# 4_cyber60-smk_periferals.net
KiCad netlist of a schematic drawn in Altium Designer
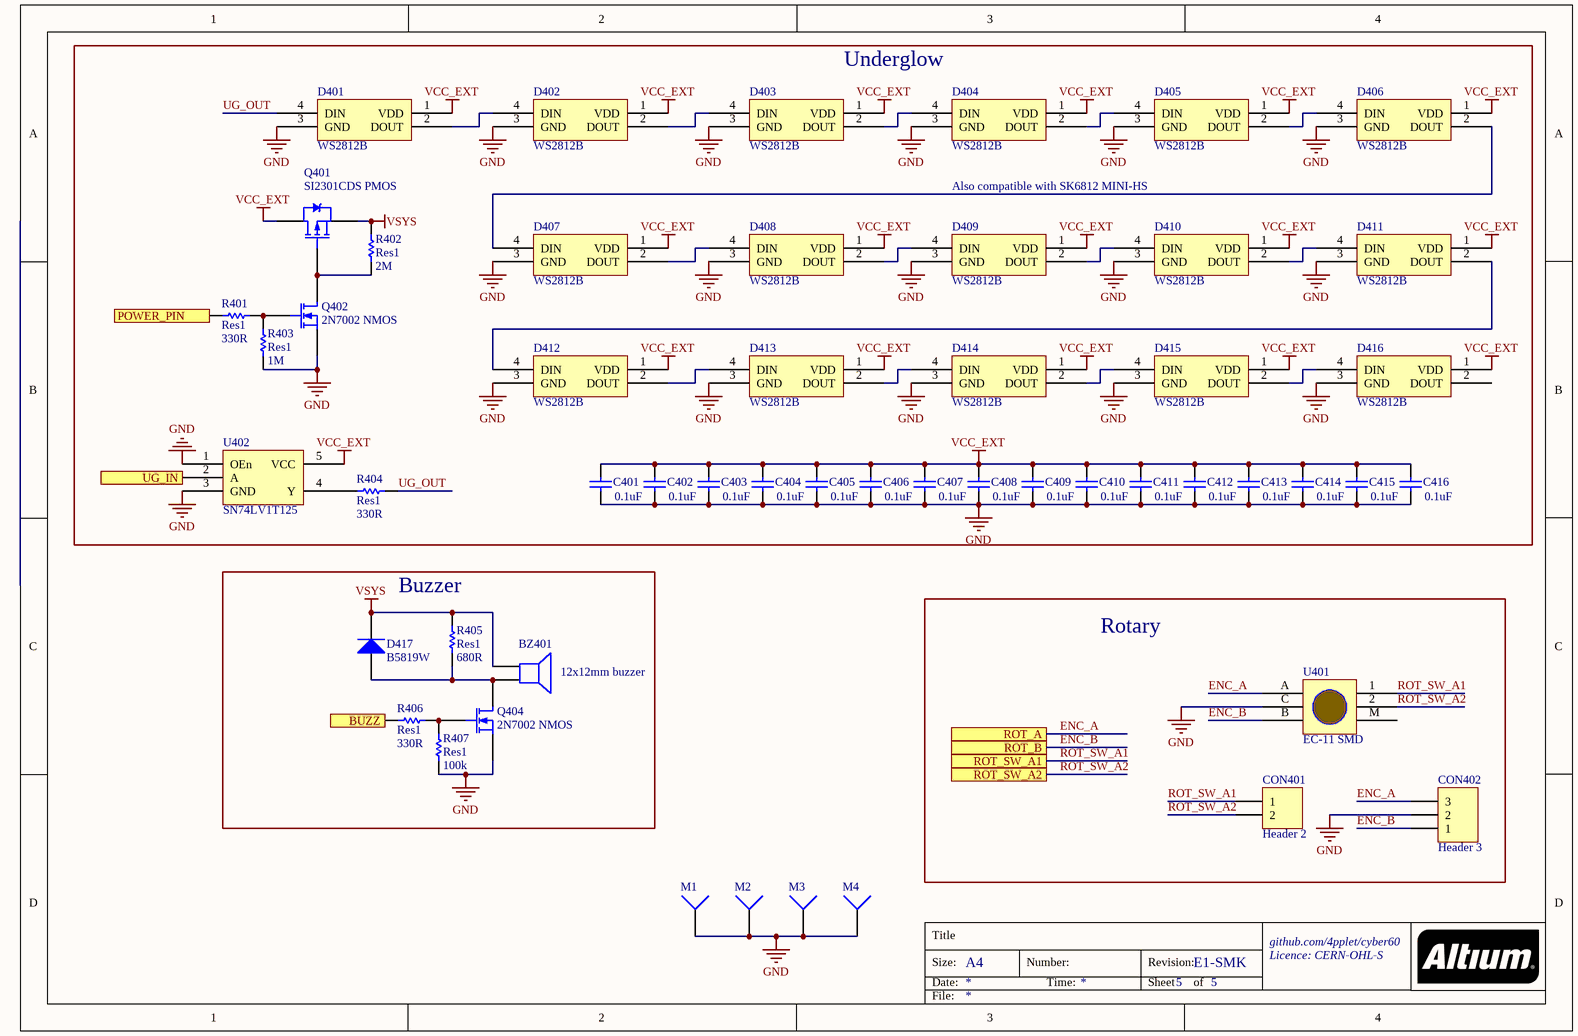
[diagram p0: 4_cyber60-smk_periferals.SchDoc]

(export (version "E")
  (design (tool "Eeschema 10.0.6"))
  (components
    (comp (ref "BZ401")
      (value "12x12mm buzzer")
      (footprint "buzzer 12x12")
      (description "Loudspeaker")
      (fields (field (name "LCSC PART #") "C409829") (field (name "MRF.PART") "YS-SBZ1230"))
      (libsource (lib "Miscellaneous Devices") (part "Speaker"))
    )
    (comp (ref "C401")
      (value "0.1uF")
      (footprint "C0603[1608]")
      (description "Capacitor")
      (fields (field (name "MFG") "KEMET") (field (name "LCSC PART #") "C14663"))
      (libsource (lib "Miscellaneous Devices") (part "Cap"))
    )
    (comp (ref "C402")
      (value "0.1uF")
      (footprint "C0603[1608]")
      (description "Capacitor")
      (fields (field (name "MFG") "KEMET") (field (name "LCSC PART #") "C14663"))
      (libsource (lib "Miscellaneous Devices") (part "Cap"))
    )
    (comp (ref "C403")
      (value "0.1uF")
      (footprint "C0603[1608]")
      (description "Capacitor")
      (fields (field (name "MFG") "KEMET") (field (name "LCSC PART #") "C14663"))
      (libsource (lib "Miscellaneous Devices") (part "Cap"))
    )
    (comp (ref "C404")
      (value "0.1uF")
      (footprint "C0603[1608]")
      (description "Capacitor")
      (fields (field (name "MFG") "KEMET") (field (name "LCSC PART #") "C14663"))
      (libsource (lib "Miscellaneous Devices") (part "Cap"))
    )
    (comp (ref "C405")
      (value "0.1uF")
      (footprint "C0603[1608]")
      (description "Capacitor")
      (fields (field (name "MFG") "KEMET") (field (name "LCSC PART #") "C14663"))
      (libsource (lib "Miscellaneous Devices") (part "Cap"))
    )
    (comp (ref "C406")
      (value "0.1uF")
      (footprint "C0603[1608]")
      (description "Capacitor")
      (fields (field (name "MFG") "KEMET") (field (name "LCSC PART #") "C14663"))
      (libsource (lib "Miscellaneous Devices") (part "Cap"))
    )
    (comp (ref "C407")
      (value "0.1uF")
      (footprint "C0603[1608]")
      (description "Capacitor")
      (fields (field (name "MFG") "KEMET") (field (name "LCSC PART #") "C14663"))
      (libsource (lib "Miscellaneous Devices") (part "Cap"))
    )
    (comp (ref "C408")
      (value "0.1uF")
      (footprint "C0603[1608]")
      (description "Capacitor")
      (fields (field (name "MFG") "KEMET") (field (name "LCSC PART #") "C14663"))
      (libsource (lib "Miscellaneous Devices") (part "Cap"))
    )
    (comp (ref "C409")
      (value "0.1uF")
      (footprint "C0603[1608]")
      (description "Capacitor")
      (fields (field (name "MFG") "KEMET") (field (name "LCSC PART #") "C14663"))
      (libsource (lib "Miscellaneous Devices") (part "Cap"))
    )
    (comp (ref "C410")
      (value "0.1uF")
      (footprint "C0603[1608]")
      (description "Capacitor")
      (fields (field (name "MFG") "KEMET") (field (name "LCSC PART #") "C14663"))
      (libsource (lib "Miscellaneous Devices") (part "Cap"))
    )
    (comp (ref "C411")
      (value "0.1uF")
      (footprint "C0603[1608]")
      (description "Capacitor")
      (fields (field (name "MFG") "KEMET") (field (name "LCSC PART #") "C14663"))
      (libsource (lib "Miscellaneous Devices") (part "Cap"))
    )
    (comp (ref "C412")
      (value "0.1uF")
      (footprint "C0603[1608]")
      (description "Capacitor")
      (fields (field (name "MFG") "KEMET") (field (name "LCSC PART #") "C14663"))
      (libsource (lib "Miscellaneous Devices") (part "Cap"))
    )
    (comp (ref "C413")
      (value "0.1uF")
      (footprint "C0603[1608]")
      (description "Capacitor")
      (fields (field (name "MFG") "KEMET") (field (name "LCSC PART #") "C14663"))
      (libsource (lib "Miscellaneous Devices") (part "Cap"))
    )
    (comp (ref "C414")
      (value "0.1uF")
      (footprint "C0603[1608]")
      (description "Capacitor")
      (fields (field (name "MFG") "KEMET") (field (name "LCSC PART #") "C14663"))
      (libsource (lib "Miscellaneous Devices") (part "Cap"))
    )
    (comp (ref "C415")
      (value "0.1uF")
      (footprint "C0603[1608]")
      (description "Capacitor")
      (fields (field (name "MFG") "KEMET") (field (name "LCSC PART #") "C14663"))
      (libsource (lib "Miscellaneous Devices") (part "Cap"))
    )
    (comp (ref "C416")
      (value "0.1uF")
      (footprint "C0603[1608]")
      (description "Capacitor")
      (fields (field (name "MFG") "KEMET") (field (name "LCSC PART #") "C14663"))
      (libsource (lib "Miscellaneous Devices") (part "Cap"))
    )
    (comp (ref "CON401")
      (value "Header 2")
      (footprint "HDR1X2")
      (description "Header, 2-Pin")
      (libsource (lib "Miscellaneous Connectors") (part "Header 2"))
    )
    (comp (ref "CON402")
      (value "Header 3")
      (footprint "HDR1X3")
      (description "Header, 3-Pin")
      (libsource (lib "Miscellaneous Connectors") (part "Header 3"))
    )
    (comp (ref "D401")
      (value "WS2812B")
      (footprint "WS2812B - 2020")
      (fields (field (name "LCSC PART #") "C965556") (field (name "MRF.PART") "WS2812C-2020"))
      (libsource (lib "Keebs") (part "WS2812B"))
    )
    (comp (ref "D402")
      (value "WS2812B")
      (footprint "WS2812B - 2020")
      (fields (field (name "LCSC PART #") "C965556") (field (name "MRF.PART") "WS2812C-2020"))
      (libsource (lib "Keebs") (part "WS2812B"))
    )
    (comp (ref "D403")
      (value "WS2812B")
      (footprint "WS2812B - 2020")
      (fields (field (name "LCSC PART #") "C965556") (field (name "MRF.PART") "WS2812C-2020"))
      (libsource (lib "Keebs") (part "WS2812B"))
    )
    (comp (ref "D404")
      (value "WS2812B")
      (footprint "WS2812B - 2020")
      (fields (field (name "LCSC PART #") "C965556") (field (name "MRF.PART") "WS2812C-2020"))
      (libsource (lib "Keebs") (part "WS2812B"))
    )
    (comp (ref "D405")
      (value "WS2812B")
      (footprint "WS2812B - 2020")
      (fields (field (name "LCSC PART #") "C965556") (field (name "MRF.PART") "WS2812C-2020"))
      (libsource (lib "Keebs") (part "WS2812B"))
    )
    (comp (ref "D406")
      (value "WS2812B")
      (footprint "WS2812B - 2020")
      (fields (field (name "LCSC PART #") "C965556") (field (name "MRF.PART") "WS2812C-2020"))
      (libsource (lib "Keebs") (part "WS2812B"))
    )
    (comp (ref "D407")
      (value "WS2812B")
      (footprint "WS2812B - 2020")
      (fields (field (name "LCSC PART #") "C965556") (field (name "MRF.PART") "WS2812C-2020"))
      (libsource (lib "Keebs") (part "WS2812B"))
    )
    (comp (ref "D408")
      (value "WS2812B")
      (footprint "WS2812B - 2020")
      (fields (field (name "LCSC PART #") "C965556") (field (name "MRF.PART") "WS2812C-2020"))
      (libsource (lib "Keebs") (part "WS2812B"))
    )
    (comp (ref "D409")
      (value "WS2812B")
      (footprint "WS2812B - 2020")
      (fields (field (name "LCSC PART #") "C965556") (field (name "MRF.PART") "WS2812C-2020"))
      (libsource (lib "Keebs") (part "WS2812B"))
    )
    (comp (ref "D410")
      (value "WS2812B")
      (footprint "WS2812B - 2020")
      (fields (field (name "LCSC PART #") "C965556") (field (name "MRF.PART") "WS2812C-2020"))
      (libsource (lib "Keebs") (part "WS2812B"))
    )
    (comp (ref "D411")
      (value "WS2812B")
      (footprint "WS2812B - 2020")
      (fields (field (name "LCSC PART #") "C965556") (field (name "MRF.PART") "WS2812C-2020"))
      (libsource (lib "Keebs") (part "WS2812B"))
    )
    (comp (ref "D412")
      (value "WS2812B")
      (footprint "WS2812B - 2020")
      (fields (field (name "LCSC PART #") "C965556") (field (name "MRF.PART") "WS2812C-2020"))
      (libsource (lib "Keebs") (part "WS2812B"))
    )
    (comp (ref "D413")
      (value "WS2812B")
      (footprint "WS2812B - 2020")
      (fields (field (name "LCSC PART #") "C965556") (field (name "MRF.PART") "WS2812C-2020"))
      (libsource (lib "Keebs") (part "WS2812B"))
    )
    (comp (ref "D414")
      (value "WS2812B")
      (footprint "WS2812B - 2020")
      (fields (field (name "LCSC PART #") "C965556") (field (name "MRF.PART") "WS2812C-2020"))
      (libsource (lib "Keebs") (part "WS2812B"))
    )
    (comp (ref "D415")
      (value "WS2812B")
      (footprint "WS2812B - 2020")
      (fields (field (name "LCSC PART #") "C965556") (field (name "MRF.PART") "WS2812C-2020"))
      (libsource (lib "Keebs") (part "WS2812B"))
    )
    (comp (ref "D416")
      (value "WS2812B")
      (footprint "WS2812B - 2020")
      (fields (field (name "LCSC PART #") "C965556") (field (name "MRF.PART") "WS2812C-2020"))
      (libsource (lib "Keebs") (part "WS2812B"))
    )
    (comp (ref "D417")
      (value "B5819W")
      (footprint "SOD-123")
      (description "Default Diode")
      (fields (field (name "LCSC PART #") "C8598"))
      (libsource (lib "Miscellaneous Devices") (part "Diode"))
    )
    (comp (ref "M1")
      (value "Socket")
      (footprint "mounting_hole")
      (fields (field (name "PUBLISHER") "Altium Limited"))
      (libsource (lib "Miscellaneous Connectors") (part "Socket"))
    )
    (comp (ref "M2")
      (value "Socket")
      (footprint "mounting_hole")
      (fields (field (name "PUBLISHER") "Altium Limited"))
      (libsource (lib "Miscellaneous Connectors") (part "Socket"))
    )
    (comp (ref "M3")
      (value "Socket")
      (footprint "mounting_hole")
      (fields (field (name "PUBLISHER") "Altium Limited"))
      (libsource (lib "Miscellaneous Connectors") (part "Socket"))
    )
    (comp (ref "M4")
      (value "Socket")
      (footprint "mounting_hole")
      (fields (field (name "PUBLISHER") "Altium Limited"))
      (libsource (lib "Miscellaneous Connectors") (part "Socket"))
    )
    (comp (ref "Q401")
      (value "SI2301CDS PMOS")
      (footprint "SOT-23-3")
      (description "P-Channel Power MOSFET")
      (fields (field (name "MRF.PART") "SI2301CDS-T1-GE3") (field (name "LCSC PART #") "C10487"))
      (libsource (lib "Miscellaneous Devices") (part "PMOS-2"))
    )
    (comp (ref "Q402")
      (value "2N7002 NMOS")
      (footprint "SOT-23-3")
      (description "N-Channel MOSFET")
      (fields (field (name "LCSC PART #") "C8545") (field (name "MRF.PART") "2N7002"))
      (libsource (lib "Miscellaneous Devices") (part "MOSFET-N"))
    )
    (comp (ref "Q404")
      (value "2N7002 NMOS")
      (footprint "SOT-23-3")
      (description "N-Channel MOSFET")
      (fields (field (name "LCSC PART #") "C8545") (field (name "MRF.PART") "2N7002"))
      (libsource (lib "Miscellaneous Devices") (part "MOSFET-N"))
    )
    (comp (ref "R401")
      (value "Res1")
      (footprint "R0603[1608]")
      (description "Resistor")
      (fields
        (field (name "ALTIUM_VALUE") "330R")
        (field (name "LCSC PART #") "C23138")
        (field (name "MRF.PART") "0603WAF3300T5E")
      )
      (libsource (lib "Miscellaneous Devices") (part "Res1"))
    )
    (comp (ref "R402")
      (value "Res1")
      (footprint "R0603[1608]")
      (description "Resistor")
      (fields
        (field (name "ALTIUM_VALUE") "2M")
        (field (name "MRF.PART") "0603WAF2004T5E")
        (field (name "LCSC PART #") "C22976")
      )
      (libsource (lib "Miscellaneous Devices") (part "Res1"))
    )
    (comp (ref "R403")
      (value "Res1")
      (footprint "R0603[1608]")
      (description "Resistor")
      (fields
        (field (name "ALTIUM_VALUE") "1M")
        (field (name "MRF.PART") "0603WAF1004T5E")
        (field (name "LCSC PART #") "C22935")
      )
      (libsource (lib "Miscellaneous Devices") (part "Res1"))
    )
    (comp (ref "R404")
      (value "Res1")
      (footprint "R0603[1608]")
      (description "Resistor")
      (fields
        (field (name "ALTIUM_VALUE") "330R")
        (field (name "LCSC PART #") "C23138")
        (field (name "MRF.PART") "0603WAF3300T5E")
      )
      (libsource (lib "Miscellaneous Devices") (part "Res1"))
    )
    (comp (ref "R405")
      (value "Res1")
      (footprint "R0603[1608]")
      (description "Resistor")
      (fields
        (field (name "ALTIUM_VALUE") "680R")
        (field (name "MRF.PART") "0603WAF6800T5E")
        (field (name "LCSC PART #") "C23228")
      )
      (libsource (lib "Miscellaneous Devices") (part "Res1"))
    )
    (comp (ref "R406")
      (value "Res1")
      (footprint "R0603[1608]")
      (description "Resistor")
      (fields
        (field (name "ALTIUM_VALUE") "330R")
        (field (name "LCSC PART #") "C23138")
        (field (name "MRF.PART") "0603WAF3300T5E")
      )
      (libsource (lib "Miscellaneous Devices") (part "Res1"))
    )
    (comp (ref "R407")
      (value "Res1")
      (footprint "R0603[1608]")
      (description "Resistor")
      (fields
        (field (name "ALTIUM_VALUE") "100k")
        (field (name "MRF.PART") "0603WAF1003T5E")
        (field (name "LCSC PART #") "C25803")
      )
      (libsource (lib "Miscellaneous Devices") (part "Res1"))
    )
    (comp (ref "U401") (value "EC-11 SMD") (footprint "EC11-SMD") (libsource (lib "Keebs") (part "EC-11")))
    (comp (ref "U402")
      (value "SN74LV1T125")
      (footprint "SOT-23-5")
      (description "SN74LV1T125 or SN74LV1T34. Connect OE to GND")
      (fields (field (name "LCSC PART #") "C473338") (field (name "MRF.PART") "SN74LV1T125DBVR"))
      (libsource (lib "Keebs") (part "SN74LV1T125"))
    )
  )
  (nets
    (net (code "1") (name "/BUZZ") (class "Default")
      (node (ref "R406") (pin "2") (pinfunction "2_2") (pintype "passive"))
    )
    (net (code "2") (name "/ENC_A") (class "Default")
      (node (ref "CON402") (pin "3") (pinfunction "3_3") (pintype "passive"))
      (node (ref "U401") (pin "A") (pinfunction "B_A") (pintype "passive"))
    )
    (net (code "3") (name "/ENC_B") (class "Default")
      (node (ref "CON402") (pin "1") (pinfunction "1_1") (pintype "passive"))
      (node (ref "U401") (pin "B") (pinfunction "B_B") (pintype "passive"))
    )
    (net (code "4") (name "/POWER_PIN") (class "Default")
      (node (ref "R401") (pin "1") (pinfunction "1_1") (pintype "passive"))
    )
    (net (code "5") (name "/ROT_SW_A1") (class "Default")
      (node (ref "CON401") (pin "1") (pinfunction "1_1") (pintype "passive"))
      (node (ref "U401") (pin "1") (pinfunction "1_1") (pintype "passive"))
    )
    (net (code "6") (name "/ROT_SW_A2") (class "Default")
      (node (ref "CON401") (pin "2") (pinfunction "2_2") (pintype "passive"))
      (node (ref "U401") (pin "2") (pinfunction "2_2") (pintype "passive"))
    )
    (net (code "7") (name "/UG_IN") (class "Default")
      (node (ref "U402") (pin "2") (pinfunction "A_2") (pintype "passive"))
    )
    (net (code "8") (name "/UG_OUT") (class "Default")
      (node (ref "D401") (pin "4") (pinfunction "DIN_4") (pintype "passive"))
      (node (ref "R404") (pin "1") (pinfunction "1_1") (pintype "passive"))
    )
    (net (code "9") (name "GND") (class "Default")
      (node (ref "C401") (pin "1") (pinfunction "1_1") (pintype "passive"))
      (node (ref "C402") (pin "1") (pinfunction "1_1") (pintype "passive"))
      (node (ref "C403") (pin "1") (pinfunction "1_1") (pintype "passive"))
      (node (ref "C404") (pin "1") (pinfunction "1_1") (pintype "passive"))
      (node (ref "C405") (pin "1") (pinfunction "1_1") (pintype "passive"))
      (node (ref "C406") (pin "1") (pinfunction "1_1") (pintype "passive"))
      (node (ref "C407") (pin "1") (pinfunction "1_1") (pintype "passive"))
      (node (ref "C408") (pin "1") (pinfunction "1_1") (pintype "passive"))
      (node (ref "C409") (pin "1") (pinfunction "1_1") (pintype "passive"))
      (node (ref "C410") (pin "1") (pinfunction "1_1") (pintype "passive"))
      (node (ref "C411") (pin "1") (pinfunction "1_1") (pintype "passive"))
      (node (ref "C412") (pin "1") (pinfunction "1_1") (pintype "passive"))
      (node (ref "C413") (pin "1") (pinfunction "1_1") (pintype "passive"))
      (node (ref "C414") (pin "1") (pinfunction "1_1") (pintype "passive"))
      (node (ref "C415") (pin "1") (pinfunction "1_1") (pintype "passive"))
      (node (ref "C416") (pin "1") (pinfunction "1_1") (pintype "passive"))
      (node (ref "CON402") (pin "2") (pinfunction "2_2") (pintype "passive"))
      (node (ref "D401") (pin "3") (pinfunction "GND_3") (pintype "passive"))
      (node (ref "D402") (pin "3") (pinfunction "GND_3") (pintype "passive"))
      (node (ref "D403") (pin "3") (pinfunction "GND_3") (pintype "passive"))
      (node (ref "D404") (pin "3") (pinfunction "GND_3") (pintype "passive"))
      (node (ref "D405") (pin "3") (pinfunction "GND_3") (pintype "passive"))
      (node (ref "D406") (pin "3") (pinfunction "GND_3") (pintype "passive"))
      (node (ref "D407") (pin "3") (pinfunction "GND_3") (pintype "passive"))
      (node (ref "D408") (pin "3") (pinfunction "GND_3") (pintype "passive"))
      (node (ref "D409") (pin "3") (pinfunction "GND_3") (pintype "passive"))
      (node (ref "D410") (pin "3") (pinfunction "GND_3") (pintype "passive"))
      (node (ref "D411") (pin "3") (pinfunction "GND_3") (pintype "passive"))
      (node (ref "D412") (pin "3") (pinfunction "GND_3") (pintype "passive"))
      (node (ref "D413") (pin "3") (pinfunction "GND_3") (pintype "passive"))
      (node (ref "D414") (pin "3") (pinfunction "GND_3") (pintype "passive"))
      (node (ref "D415") (pin "3") (pinfunction "GND_3") (pintype "passive"))
      (node (ref "D416") (pin "3") (pinfunction "GND_3") (pintype "passive"))
      (node (ref "M1") (pin "1") (pinfunction "1_1") (pintype "passive"))
      (node (ref "M2") (pin "1") (pinfunction "1_1") (pintype "passive"))
      (node (ref "M3") (pin "1") (pinfunction "1_1") (pintype "passive"))
      (node (ref "M4") (pin "1") (pinfunction "1_1") (pintype "passive"))
      (node (ref "Q402") (pin "2") (pinfunction "S_2") (pintype "passive"))
      (node (ref "Q404") (pin "2") (pinfunction "S_2") (pintype "passive"))
      (node (ref "R403") (pin "2") (pinfunction "2_2") (pintype "passive"))
      (node (ref "R407") (pin "2") (pinfunction "2_2") (pintype "passive"))
      (node (ref "U401") (pin "C") (pinfunction "C_C") (pintype "passive"))
      (node (ref "U402") (pin "1") (pinfunction "OEn_1") (pintype "passive"))
      (node (ref "U402") (pin "3") (pinfunction "GND_3") (pintype "passive"))
    )
    (net (code "10") (name "Net-(D401-DOUT)") (class "Default")
      (node (ref "D401") (pin "2") (pinfunction "DOUT_2") (pintype "passive"))
      (node (ref "D402") (pin "4") (pinfunction "DIN_4") (pintype "passive"))
    )
    (net (code "11") (name "Net-(D402-DOUT)") (class "Default")
      (node (ref "D402") (pin "2") (pinfunction "DOUT_2") (pintype "passive"))
      (node (ref "D403") (pin "4") (pinfunction "DIN_4") (pintype "passive"))
    )
    (net (code "12") (name "Net-(D403-DOUT)") (class "Default")
      (node (ref "D403") (pin "2") (pinfunction "DOUT_2") (pintype "passive"))
      (node (ref "D404") (pin "4") (pinfunction "DIN_4") (pintype "passive"))
    )
    (net (code "13") (name "Net-(D404-DOUT)") (class "Default")
      (node (ref "D404") (pin "2") (pinfunction "DOUT_2") (pintype "passive"))
      (node (ref "D405") (pin "4") (pinfunction "DIN_4") (pintype "passive"))
    )
    (net (code "14") (name "Net-(D405-DOUT)") (class "Default")
      (node (ref "D405") (pin "2") (pinfunction "DOUT_2") (pintype "passive"))
      (node (ref "D406") (pin "4") (pinfunction "DIN_4") (pintype "passive"))
    )
    (net (code "15") (name "Net-(D406-DOUT)") (class "Default")
      (node (ref "D406") (pin "2") (pinfunction "DOUT_2") (pintype "passive"))
      (node (ref "D407") (pin "4") (pinfunction "DIN_4") (pintype "passive"))
    )
    (net (code "16") (name "Net-(D407-DOUT)") (class "Default")
      (node (ref "D407") (pin "2") (pinfunction "DOUT_2") (pintype "passive"))
      (node (ref "D408") (pin "4") (pinfunction "DIN_4") (pintype "passive"))
    )
    (net (code "17") (name "Net-(D408-DOUT)") (class "Default")
      (node (ref "D408") (pin "2") (pinfunction "DOUT_2") (pintype "passive"))
      (node (ref "D409") (pin "4") (pinfunction "DIN_4") (pintype "passive"))
    )
    (net (code "18") (name "Net-(D409-DOUT)") (class "Default")
      (node (ref "D409") (pin "2") (pinfunction "DOUT_2") (pintype "passive"))
      (node (ref "D410") (pin "4") (pinfunction "DIN_4") (pintype "passive"))
    )
    (net (code "19") (name "Net-(D410-DOUT)") (class "Default")
      (node (ref "D410") (pin "2") (pinfunction "DOUT_2") (pintype "passive"))
      (node (ref "D411") (pin "4") (pinfunction "DIN_4") (pintype "passive"))
    )
    (net (code "20") (name "Net-(D411-DOUT)") (class "Default")
      (node (ref "D411") (pin "2") (pinfunction "DOUT_2") (pintype "passive"))
      (node (ref "D412") (pin "4") (pinfunction "DIN_4") (pintype "passive"))
    )
    (net (code "21") (name "Net-(D412-DOUT)") (class "Default")
      (node (ref "D412") (pin "2") (pinfunction "DOUT_2") (pintype "passive"))
      (node (ref "D413") (pin "4") (pinfunction "DIN_4") (pintype "passive"))
    )
    (net (code "22") (name "Net-(D413-DOUT)") (class "Default")
      (node (ref "D413") (pin "2") (pinfunction "DOUT_2") (pintype "passive"))
      (node (ref "D414") (pin "4") (pinfunction "DIN_4") (pintype "passive"))
    )
    (net (code "23") (name "Net-(D414-DOUT)") (class "Default")
      (node (ref "D414") (pin "2") (pinfunction "DOUT_2") (pintype "passive"))
      (node (ref "D415") (pin "4") (pinfunction "DIN_4") (pintype "passive"))
    )
    (net (code "24") (name "Net-(D415-DOUT)") (class "Default")
      (node (ref "D415") (pin "2") (pinfunction "DOUT_2") (pintype "passive"))
      (node (ref "D416") (pin "4") (pinfunction "DIN_4") (pintype "passive"))
    )
    (net (code "25") (name "Net-(D417-A)") (class "Default")
      (node (ref "BZ401") (pin "2") (pinfunction "2_2") (pintype "passive"))
      (node (ref "D417") (pin "1") (pinfunction "A_1") (pintype "passive"))
      (node (ref "Q404") (pin "3") (pinfunction "D_3") (pintype "passive"))
      (node (ref "R405") (pin "2") (pinfunction "2_2") (pintype "passive"))
    )
    (net (code "26") (name "Net-(Q401-G)") (class "Default")
      (node (ref "Q401") (pin "1") (pinfunction "G_1") (pintype "passive"))
      (node (ref "Q402") (pin "3") (pinfunction "D_3") (pintype "passive"))
      (node (ref "R402") (pin "1") (pinfunction "1_1") (pintype "passive"))
    )
    (net (code "27") (name "Net-(Q402-G)") (class "Default")
      (node (ref "Q402") (pin "1") (pinfunction "G_1") (pintype "passive"))
      (node (ref "R401") (pin "2") (pinfunction "2_2") (pintype "passive"))
      (node (ref "R403") (pin "1") (pinfunction "1_1") (pintype "passive"))
    )
    (net (code "28") (name "Net-(Q404-G)") (class "Default")
      (node (ref "Q404") (pin "1") (pinfunction "G_1") (pintype "passive"))
      (node (ref "R406") (pin "1") (pinfunction "1_1") (pintype "passive"))
      (node (ref "R407") (pin "1") (pinfunction "1_1") (pintype "passive"))
    )
    (net (code "29") (name "Net-(U402-Y)") (class "Default")
      (node (ref "R404") (pin "2") (pinfunction "2_2") (pintype "passive"))
      (node (ref "U402") (pin "4") (pinfunction "Y_4") (pintype "passive"))
    )
    (net (code "30") (name "VCC_EXT") (class "Default")
      (node (ref "C401") (pin "2") (pinfunction "2_2") (pintype "passive"))
      (node (ref "C402") (pin "2") (pinfunction "2_2") (pintype "passive"))
      (node (ref "C403") (pin "2") (pinfunction "2_2") (pintype "passive"))
      (node (ref "C404") (pin "2") (pinfunction "2_2") (pintype "passive"))
      (node (ref "C405") (pin "2") (pinfunction "2_2") (pintype "passive"))
      (node (ref "C406") (pin "2") (pinfunction "2_2") (pintype "passive"))
      (node (ref "C407") (pin "2") (pinfunction "2_2") (pintype "passive"))
      (node (ref "C408") (pin "2") (pinfunction "2_2") (pintype "passive"))
      (node (ref "C409") (pin "2") (pinfunction "2_2") (pintype "passive"))
      (node (ref "C410") (pin "2") (pinfunction "2_2") (pintype "passive"))
      (node (ref "C411") (pin "2") (pinfunction "2_2") (pintype "passive"))
      (node (ref "C412") (pin "2") (pinfunction "2_2") (pintype "passive"))
      (node (ref "C413") (pin "2") (pinfunction "2_2") (pintype "passive"))
      (node (ref "C414") (pin "2") (pinfunction "2_2") (pintype "passive"))
      (node (ref "C415") (pin "2") (pinfunction "2_2") (pintype "passive"))
      (node (ref "C416") (pin "2") (pinfunction "2_2") (pintype "passive"))
      (node (ref "D401") (pin "1") (pinfunction "VDD_1") (pintype "passive"))
      (node (ref "D402") (pin "1") (pinfunction "VDD_1") (pintype "passive"))
      (node (ref "D403") (pin "1") (pinfunction "VDD_1") (pintype "passive"))
      (node (ref "D404") (pin "1") (pinfunction "VDD_1") (pintype "passive"))
      (node (ref "D405") (pin "1") (pinfunction "VDD_1") (pintype "passive"))
      (node (ref "D406") (pin "1") (pinfunction "VDD_1") (pintype "passive"))
      (node (ref "D407") (pin "1") (pinfunction "VDD_1") (pintype "passive"))
      (node (ref "D408") (pin "1") (pinfunction "VDD_1") (pintype "passive"))
      (node (ref "D409") (pin "1") (pinfunction "VDD_1") (pintype "passive"))
      (node (ref "D410") (pin "1") (pinfunction "VDD_1") (pintype "passive"))
      (node (ref "D411") (pin "1") (pinfunction "VDD_1") (pintype "passive"))
      (node (ref "D412") (pin "1") (pinfunction "VDD_1") (pintype "passive"))
      (node (ref "D413") (pin "1") (pinfunction "VDD_1") (pintype "passive"))
      (node (ref "D414") (pin "1") (pinfunction "VDD_1") (pintype "passive"))
      (node (ref "D415") (pin "1") (pinfunction "VDD_1") (pintype "passive"))
      (node (ref "D416") (pin "1") (pinfunction "VDD_1") (pintype "passive"))
      (node (ref "Q401") (pin "3") (pinfunction "D_3") (pintype "passive"))
      (node (ref "U402") (pin "5") (pinfunction "VCC_5") (pintype "passive"))
    )
    (net (code "31") (name "VSYS") (class "Default")
      (node (ref "BZ401") (pin "1") (pinfunction "1_1") (pintype "passive"))
      (node (ref "D417") (pin "2") (pinfunction "K_2") (pintype "passive"))
      (node (ref "Q401") (pin "2") (pinfunction "S_2") (pintype "passive"))
      (node (ref "R402") (pin "2") (pinfunction "2_2") (pintype "passive"))
      (node (ref "R405") (pin "1") (pinfunction "1_1") (pintype "passive"))
    )
    (net (code "32") (name "unconnected-(D416-DOUT-Pad2)") (class "Default")
      (node (ref "D416") (pin "2") (pinfunction "DOUT_2") (pintype "passive"))
    )
    (net (code "33") (name "unconnected-(U401-PadM)") (class "Default")
      (node (ref "U401") (pin "M") (pinfunction "M_M") (pintype "passive"))
    )
  )
)
